# version1.net
KiCad netlist of a schematic drawn in EAGLE
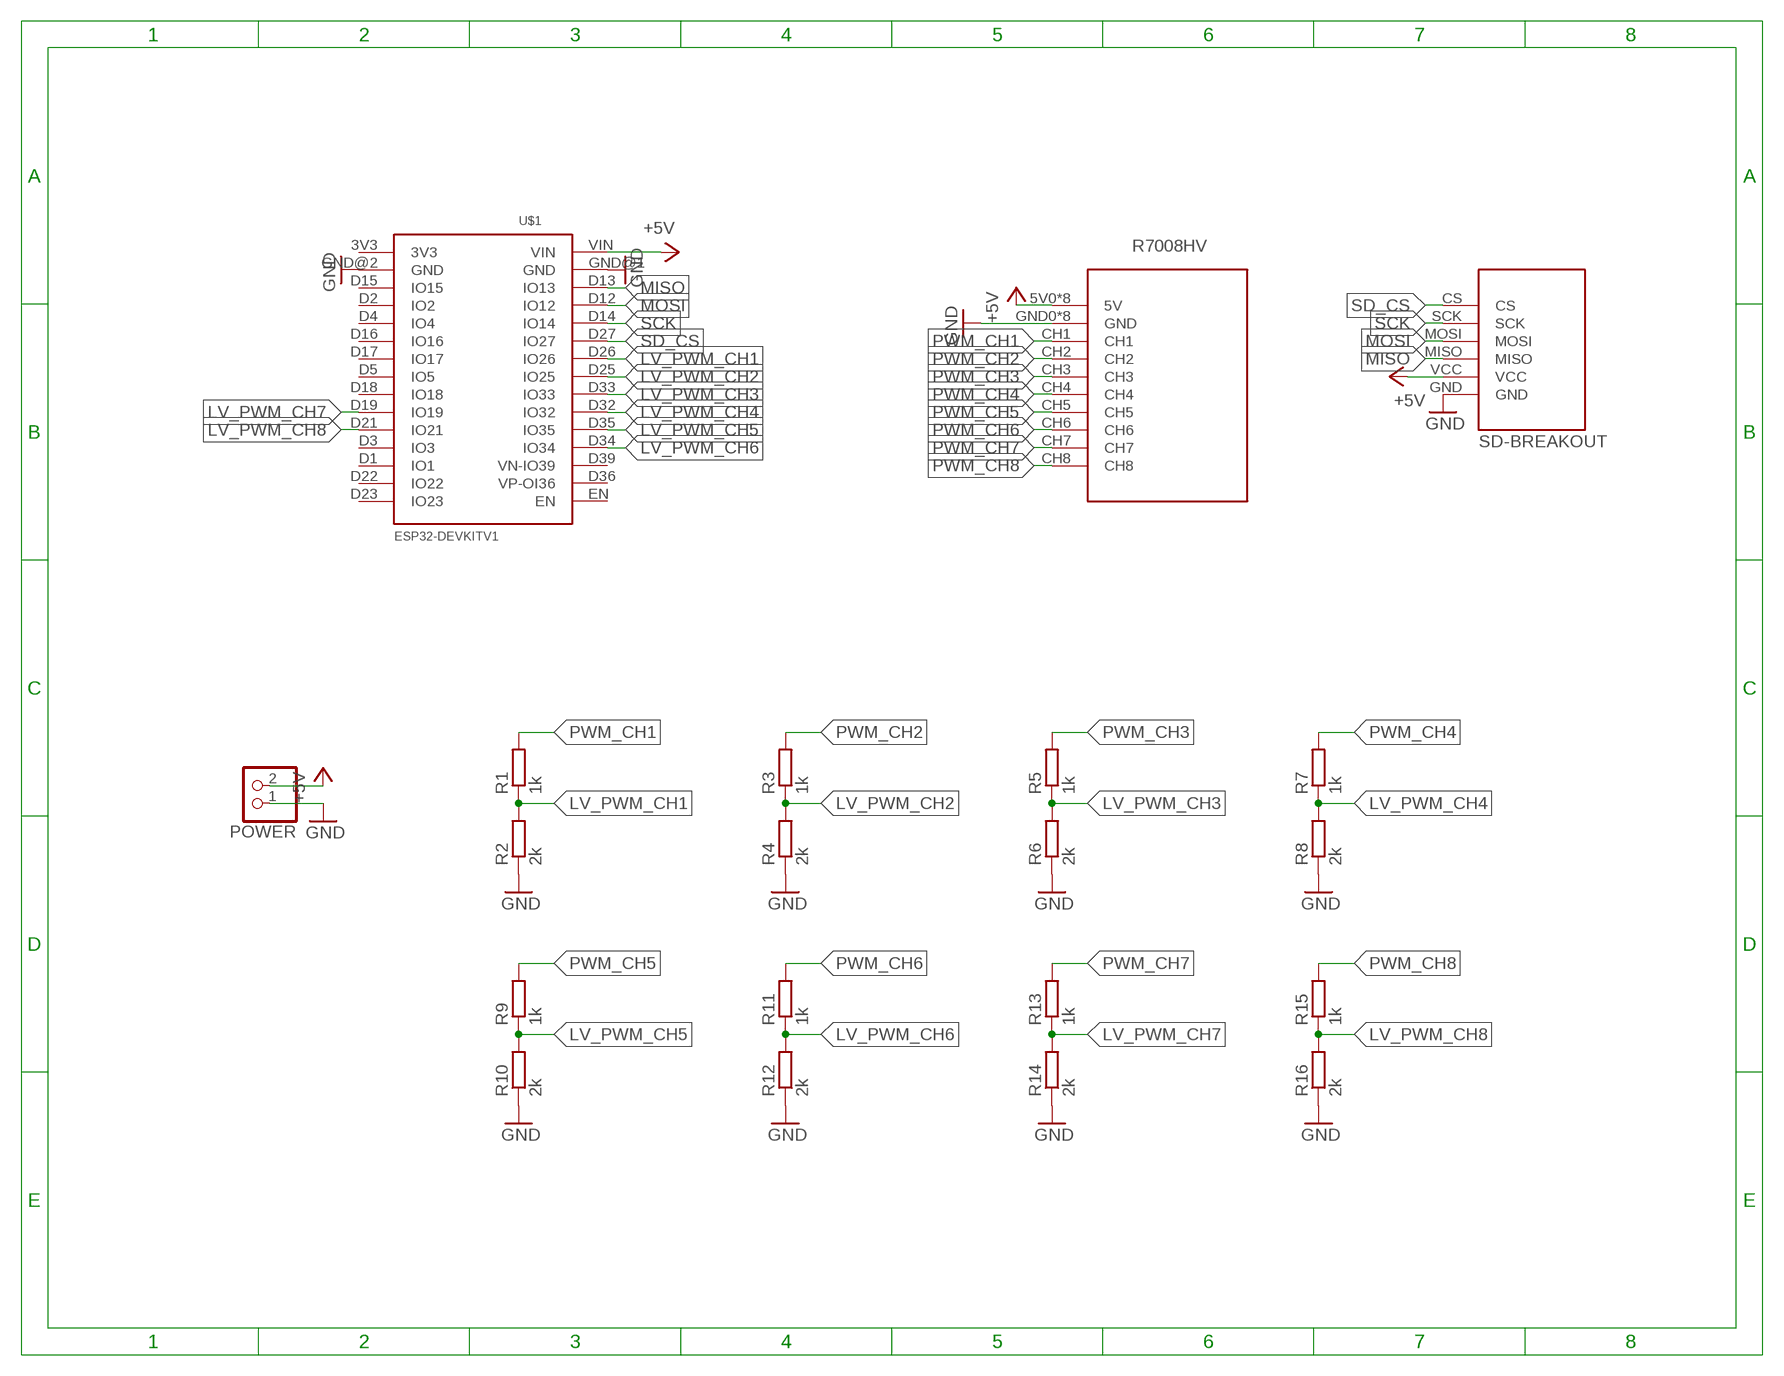
[diagram p0: schematic, sheet 1]

(export (version "E")
  (design (tool "Eeschema 10.0.6"))
  (components
    (comp (ref "POWER")
      (value "PINHD-1X2")
      (footprint "eagle-import:1X02")
      (libsource (lib "eagle-import") (part "PINHD-1X2"))
    )
    (comp (ref "R1")
      (value "1k")
      (footprint "eagle-import:0207_7")
      (libsource (lib "eagle-import") (part "R-EU_0207/7"))
    )
    (comp (ref "R2")
      (value "2k")
      (footprint "eagle-import:0207_7")
      (libsource (lib "eagle-import") (part "R-EU_0207/7"))
    )
    (comp (ref "R3")
      (value "1k")
      (footprint "eagle-import:0207_7")
      (libsource (lib "eagle-import") (part "R-EU_0207/7"))
    )
    (comp (ref "R4")
      (value "2k")
      (footprint "eagle-import:0207_7")
      (libsource (lib "eagle-import") (part "R-EU_0207/7"))
    )
    (comp (ref "R5")
      (value "1k")
      (footprint "eagle-import:0207_7")
      (libsource (lib "eagle-import") (part "R-EU_0207/7"))
    )
    (comp (ref "R6")
      (value "2k")
      (footprint "eagle-import:0207_7")
      (libsource (lib "eagle-import") (part "R-EU_0207/7"))
    )
    (comp (ref "R7")
      (value "1k")
      (footprint "eagle-import:0207_7")
      (libsource (lib "eagle-import") (part "R-EU_0207/7"))
    )
    (comp (ref "R8")
      (value "2k")
      (footprint "eagle-import:0207_7")
      (libsource (lib "eagle-import") (part "R-EU_0207/7"))
    )
    (comp (ref "R9")
      (value "1k")
      (footprint "eagle-import:0207_7")
      (libsource (lib "eagle-import") (part "R-EU_0207/7"))
    )
    (comp (ref "R10")
      (value "2k")
      (footprint "eagle-import:0207_7")
      (libsource (lib "eagle-import") (part "R-EU_0207/7"))
    )
    (comp (ref "R11")
      (value "1k")
      (footprint "eagle-import:0207_7")
      (libsource (lib "eagle-import") (part "R-EU_0207/7"))
    )
    (comp (ref "R12")
      (value "2k")
      (footprint "eagle-import:0207_7")
      (libsource (lib "eagle-import") (part "R-EU_0207/7"))
    )
    (comp (ref "R13")
      (value "1k")
      (footprint "eagle-import:0207_7")
      (libsource (lib "eagle-import") (part "R-EU_0207/7"))
    )
    (comp (ref "R14")
      (value "2k")
      (footprint "eagle-import:0207_7")
      (libsource (lib "eagle-import") (part "R-EU_0207/7"))
    )
    (comp (ref "R15")
      (value "1k")
      (footprint "eagle-import:0207_7")
      (libsource (lib "eagle-import") (part "R-EU_0207/7"))
    )
    (comp (ref "R16")
      (value "2k")
      (footprint "eagle-import:0207_7")
      (libsource (lib "eagle-import") (part "R-EU_0207/7"))
    )
    (comp (ref "U$1")
      (value "ESP32DEVKITV1")
      (footprint "eagle-import:ESP32-DEVKITV1")
      (libsource (lib "eagle-import") (part "ESP32DEVKITV1"))
    )
    (comp (ref "U$2")
      (value "HKD-MICRO-SD-BREAKOUTV")
      (footprint "eagle-import:HKD-MICRO-SD-BREAKOUT-VERTICAL")
      (libsource (lib "eagle-import") (part "HKD-MICRO-SD-BREAKOUTV"))
    )
    (comp (ref "U$3")
      (value "R7008HV")
      (footprint "eagle-import:R7008HV")
      (libsource (lib "eagle-import") (part "R7008HV"))
    )
  )
  (nets
    (net (code "1") (name "+5V") (class "Default")
      (node (ref "POWER") (pin "2") (pinfunction "2_2") (pintype "passive"))
      (node (ref "U$1") (pin "VIN") (pinfunction "VIN_VIN") (pintype "bidirectional"))
      (node (ref "U$2") (pin "VCC") (pinfunction "VCC_VCC") (pintype "bidirectional"))
      (node (ref "U$3") (pin "5V0") (pinfunction "5V_5V0") (pintype "bidirectional"))
      (node (ref "U$3") (pin "5V1") (pinfunction "5V_5V1") (pintype "bidirectional"))
      (node (ref "U$3") (pin "5V2") (pinfunction "5V_5V2") (pintype "bidirectional"))
      (node (ref "U$3") (pin "5V3") (pinfunction "5V_5V3") (pintype "bidirectional"))
      (node (ref "U$3") (pin "5V4") (pinfunction "5V_5V4") (pintype "bidirectional"))
      (node (ref "U$3") (pin "5V5") (pinfunction "5V_5V5") (pintype "bidirectional"))
      (node (ref "U$3") (pin "5V6") (pinfunction "5V_5V6") (pintype "bidirectional"))
      (node (ref "U$3") (pin "5V7") (pinfunction "5V_5V7") (pintype "bidirectional"))
    )
    (net (code "2") (name "GND") (class "Default")
      (node (ref "POWER") (pin "1") (pinfunction "1_1") (pintype "passive"))
      (node (ref "R10") (pin "1") (pinfunction "1_1") (pintype "passive"))
      (node (ref "R12") (pin "1") (pinfunction "1_1") (pintype "passive"))
      (node (ref "R14") (pin "1") (pinfunction "1_1") (pintype "passive"))
      (node (ref "R16") (pin "1") (pinfunction "1_1") (pintype "passive"))
      (node (ref "R2") (pin "1") (pinfunction "1_1") (pintype "passive"))
      (node (ref "R4") (pin "1") (pinfunction "1_1") (pintype "passive"))
      (node (ref "R6") (pin "1") (pinfunction "1_1") (pintype "passive"))
      (node (ref "R8") (pin "1") (pinfunction "1_1") (pintype "passive"))
      (node (ref "U$1") (pin "GND@1") (pinfunction "GND_GND@1") (pintype "bidirectional"))
      (node (ref "U$1") (pin "GND@2") (pinfunction "GND_GND@2") (pintype "bidirectional"))
      (node (ref "U$2") (pin "GND") (pinfunction "GND_GND") (pintype "bidirectional"))
      (node (ref "U$3") (pin "GND0") (pinfunction "GND_GND0") (pintype "bidirectional"))
      (node (ref "U$3") (pin "GND1") (pinfunction "GND_GND1") (pintype "bidirectional"))
      (node (ref "U$3") (pin "GND2") (pinfunction "GND_GND2") (pintype "bidirectional"))
      (node (ref "U$3") (pin "GND3") (pinfunction "GND_GND3") (pintype "bidirectional"))
      (node (ref "U$3") (pin "GND4") (pinfunction "GND_GND4") (pintype "bidirectional"))
      (node (ref "U$3") (pin "GND5") (pinfunction "GND_GND5") (pintype "bidirectional"))
      (node (ref "U$3") (pin "GND6") (pinfunction "GND_GND6") (pintype "bidirectional"))
      (node (ref "U$3") (pin "GND7") (pinfunction "GND_GND7") (pintype "bidirectional"))
    )
    (net (code "3") (name "LV_PWM_CH1") (class "Default")
      (node (ref "R1") (pin "1") (pinfunction "1_1") (pintype "passive"))
      (node (ref "R2") (pin "2") (pinfunction "2_2") (pintype "passive"))
      (node (ref "U$1") (pin "D26") (pinfunction "IO26_D26") (pintype "bidirectional"))
    )
    (net (code "4") (name "LV_PWM_CH2") (class "Default")
      (node (ref "R3") (pin "1") (pinfunction "1_1") (pintype "passive"))
      (node (ref "R4") (pin "2") (pinfunction "2_2") (pintype "passive"))
      (node (ref "U$1") (pin "D25") (pinfunction "IO25_D25") (pintype "bidirectional"))
    )
    (net (code "5") (name "LV_PWM_CH3") (class "Default")
      (node (ref "R5") (pin "1") (pinfunction "1_1") (pintype "passive"))
      (node (ref "R6") (pin "2") (pinfunction "2_2") (pintype "passive"))
      (node (ref "U$1") (pin "D33") (pinfunction "IO33_D33") (pintype "bidirectional"))
    )
    (net (code "6") (name "LV_PWM_CH4") (class "Default")
      (node (ref "R7") (pin "1") (pinfunction "1_1") (pintype "passive"))
      (node (ref "R8") (pin "2") (pinfunction "2_2") (pintype "passive"))
      (node (ref "U$1") (pin "D32") (pinfunction "IO32_D32") (pintype "bidirectional"))
    )
    (net (code "7") (name "LV_PWM_CH5") (class "Default")
      (node (ref "R10") (pin "2") (pinfunction "2_2") (pintype "passive"))
      (node (ref "R9") (pin "1") (pinfunction "1_1") (pintype "passive"))
      (node (ref "U$1") (pin "D35") (pinfunction "IO35_D35") (pintype "bidirectional"))
    )
    (net (code "8") (name "LV_PWM_CH6") (class "Default")
      (node (ref "R11") (pin "1") (pinfunction "1_1") (pintype "passive"))
      (node (ref "R12") (pin "2") (pinfunction "2_2") (pintype "passive"))
      (node (ref "U$1") (pin "D34") (pinfunction "IO34_D34") (pintype "bidirectional"))
    )
    (net (code "9") (name "LV_PWM_CH7") (class "Default")
      (node (ref "R13") (pin "1") (pinfunction "1_1") (pintype "passive"))
      (node (ref "R14") (pin "2") (pinfunction "2_2") (pintype "passive"))
      (node (ref "U$1") (pin "D19") (pinfunction "IO19_D19") (pintype "bidirectional"))
    )
    (net (code "10") (name "LV_PWM_CH8") (class "Default")
      (node (ref "R15") (pin "1") (pinfunction "1_1") (pintype "passive"))
      (node (ref "R16") (pin "2") (pinfunction "2_2") (pintype "passive"))
      (node (ref "U$1") (pin "D21") (pinfunction "IO21_D21") (pintype "bidirectional"))
    )
    (net (code "11") (name "MISO") (class "Default")
      (node (ref "U$1") (pin "D13") (pinfunction "IO13_D13") (pintype "bidirectional"))
      (node (ref "U$2") (pin "MISO") (pinfunction "MISO_MISO") (pintype "bidirectional"))
    )
    (net (code "12") (name "MOSI") (class "Default")
      (node (ref "U$1") (pin "D12") (pinfunction "IO12_D12") (pintype "bidirectional"))
      (node (ref "U$2") (pin "MOSI") (pinfunction "MOSI_MOSI") (pintype "bidirectional"))
    )
    (net (code "13") (name "PWM_CH1") (class "Default")
      (node (ref "R1") (pin "2") (pinfunction "2_2") (pintype "passive"))
      (node (ref "U$3") (pin "CH1") (pinfunction "CH1_CH1") (pintype "bidirectional"))
    )
    (net (code "14") (name "PWM_CH2") (class "Default")
      (node (ref "R3") (pin "2") (pinfunction "2_2") (pintype "passive"))
      (node (ref "U$3") (pin "CH2") (pinfunction "CH2_CH2") (pintype "bidirectional"))
    )
    (net (code "15") (name "PWM_CH3") (class "Default")
      (node (ref "R5") (pin "2") (pinfunction "2_2") (pintype "passive"))
      (node (ref "U$3") (pin "CH3") (pinfunction "CH3_CH3") (pintype "bidirectional"))
    )
    (net (code "16") (name "PWM_CH4") (class "Default")
      (node (ref "R7") (pin "2") (pinfunction "2_2") (pintype "passive"))
      (node (ref "U$3") (pin "CH4") (pinfunction "CH4_CH4") (pintype "bidirectional"))
    )
    (net (code "17") (name "PWM_CH5") (class "Default")
      (node (ref "R9") (pin "2") (pinfunction "2_2") (pintype "passive"))
      (node (ref "U$3") (pin "CH5") (pinfunction "CH5_CH5") (pintype "bidirectional"))
    )
    (net (code "18") (name "PWM_CH6") (class "Default")
      (node (ref "R11") (pin "2") (pinfunction "2_2") (pintype "passive"))
      (node (ref "U$3") (pin "CH6") (pinfunction "CH6_CH6") (pintype "bidirectional"))
    )
    (net (code "19") (name "PWM_CH7") (class "Default")
      (node (ref "R13") (pin "2") (pinfunction "2_2") (pintype "passive"))
      (node (ref "U$3") (pin "CH7") (pinfunction "CH7_CH7") (pintype "bidirectional"))
    )
    (net (code "20") (name "PWM_CH8") (class "Default")
      (node (ref "R15") (pin "2") (pinfunction "2_2") (pintype "passive"))
      (node (ref "U$3") (pin "CH8") (pinfunction "CH8_CH8") (pintype "bidirectional"))
    )
    (net (code "21") (name "SCK") (class "Default")
      (node (ref "U$1") (pin "D14") (pinfunction "IO14_D14") (pintype "bidirectional"))
      (node (ref "U$2") (pin "SCK") (pinfunction "SCK_SCK") (pintype "bidirectional"))
    )
    (net (code "22") (name "SD_CS") (class "Default")
      (node (ref "U$1") (pin "D27") (pinfunction "IO27_D27") (pintype "bidirectional"))
      (node (ref "U$2") (pin "CS") (pinfunction "CS_CS") (pintype "bidirectional"))
    )
    (net (code "23") (name "unconnected-(U$1-IO1-PadD1)") (class "Default")
      (node (ref "U$1") (pin "D1") (pinfunction "IO1_D1") (pintype "bidirectional"))
    )
    (net (code "24") (name "unconnected-(U$1-IO2-PadD2)") (class "Default")
      (node (ref "U$1") (pin "D2") (pinfunction "IO2_D2") (pintype "bidirectional"))
    )
    (net (code "25") (name "unconnected-(U$1-IO3-PadD3)") (class "Default")
      (node (ref "U$1") (pin "D3") (pinfunction "IO3_D3") (pintype "bidirectional"))
    )
    (net (code "26") (name "unconnected-(U$1-IO4-PadD4)") (class "Default")
      (node (ref "U$1") (pin "D4") (pinfunction "IO4_D4") (pintype "bidirectional"))
    )
    (net (code "27") (name "unconnected-(U$1-IO5-PadD5)") (class "Default")
      (node (ref "U$1") (pin "D5") (pinfunction "IO5_D5") (pintype "bidirectional"))
    )
    (net (code "28") (name "unconnected-(U$1-IO15-PadD15)") (class "Default")
      (node (ref "U$1") (pin "D15") (pinfunction "IO15_D15") (pintype "bidirectional"))
    )
    (net (code "29") (name "unconnected-(U$1-IO16-PadD16)") (class "Default")
      (node (ref "U$1") (pin "D16") (pinfunction "IO16_D16") (pintype "bidirectional"))
    )
    (net (code "30") (name "unconnected-(U$1-IO17-PadD17)") (class "Default")
      (node (ref "U$1") (pin "D17") (pinfunction "IO17_D17") (pintype "bidirectional"))
    )
    (net (code "31") (name "unconnected-(U$1-IO18-PadD18)") (class "Default")
      (node (ref "U$1") (pin "D18") (pinfunction "IO18_D18") (pintype "bidirectional"))
    )
    (net (code "32") (name "unconnected-(U$1-IO22-PadD22)") (class "Default")
      (node (ref "U$1") (pin "D22") (pinfunction "IO22_D22") (pintype "bidirectional"))
    )
    (net (code "33") (name "unconnected-(U$1-IO23-PadD23)") (class "Default")
      (node (ref "U$1") (pin "D23") (pinfunction "IO23_D23") (pintype "bidirectional"))
    )
    (net (code "34") (name "unconnected-(U$1-Pad3V3)") (class "Default")
      (node (ref "U$1") (pin "3V3") (pinfunction "3V3_3V3") (pintype "bidirectional"))
    )
    (net (code "35") (name "unconnected-(U$1-PadEN)") (class "Default")
      (node (ref "U$1") (pin "EN") (pinfunction "EN_EN") (pintype "bidirectional"))
    )
    (net (code "36") (name "unconnected-(U$1-VN-IO39-PadD39)") (class "Default")
      (node (ref "U$1") (pin "D39") (pinfunction "VN-IO39_D39") (pintype "bidirectional"))
    )
    (net (code "37") (name "unconnected-(U$1-VP-OI36-PadD36)") (class "Default")
      (node (ref "U$1") (pin "D36") (pinfunction "VP-OI36_D36") (pintype "bidirectional"))
    )
  )
)
